# POWER.net
KiCad netlist of a schematic drawn in Altium Designer
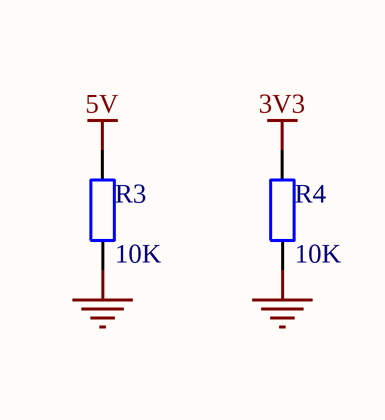
[diagram p0: POWER.SchDoc]

(export (version "E")
  (design (tool "Eeschema 10.0.6"))
  (components
    (comp (ref "R3")
      (value "10K")
      (footprint "AXIAL-0.4")
      (description "Resistor")
      (fields (field (name "Comment") "Res2") (field (name "PUBLISHER") "Altium Limited"))
      (libsource (lib "Miscellaneous Devices") (part "Res2"))
    )
    (comp (ref "R4")
      (value "10K")
      (footprint "AXIAL-0.4")
      (description "Resistor")
      (fields (field (name "Comment") "Res2") (field (name "PUBLISHER") "Altium Limited"))
      (libsource (lib "Miscellaneous Devices") (part "Res2"))
    )
  )
  (nets
    (net (code "1") (name "3V3") (class "Default")
      (node (ref "R4") (pin "2") (pinfunction "2_2") (pintype "passive"))
    )
    (net (code "2") (name "5V") (class "Default")
      (node (ref "R3") (pin "2") (pinfunction "2_2") (pintype "passive"))
    )
    (net (code "3") (name "GND") (class "Default")
      (node (ref "R3") (pin "1") (pinfunction "1_1") (pintype "passive"))
      (node (ref "R4") (pin "1") (pinfunction "1_1") (pintype "passive"))
    )
  )
)
